# overdrive.net
KiCad netlist of a schematic drawn in Altium Designer
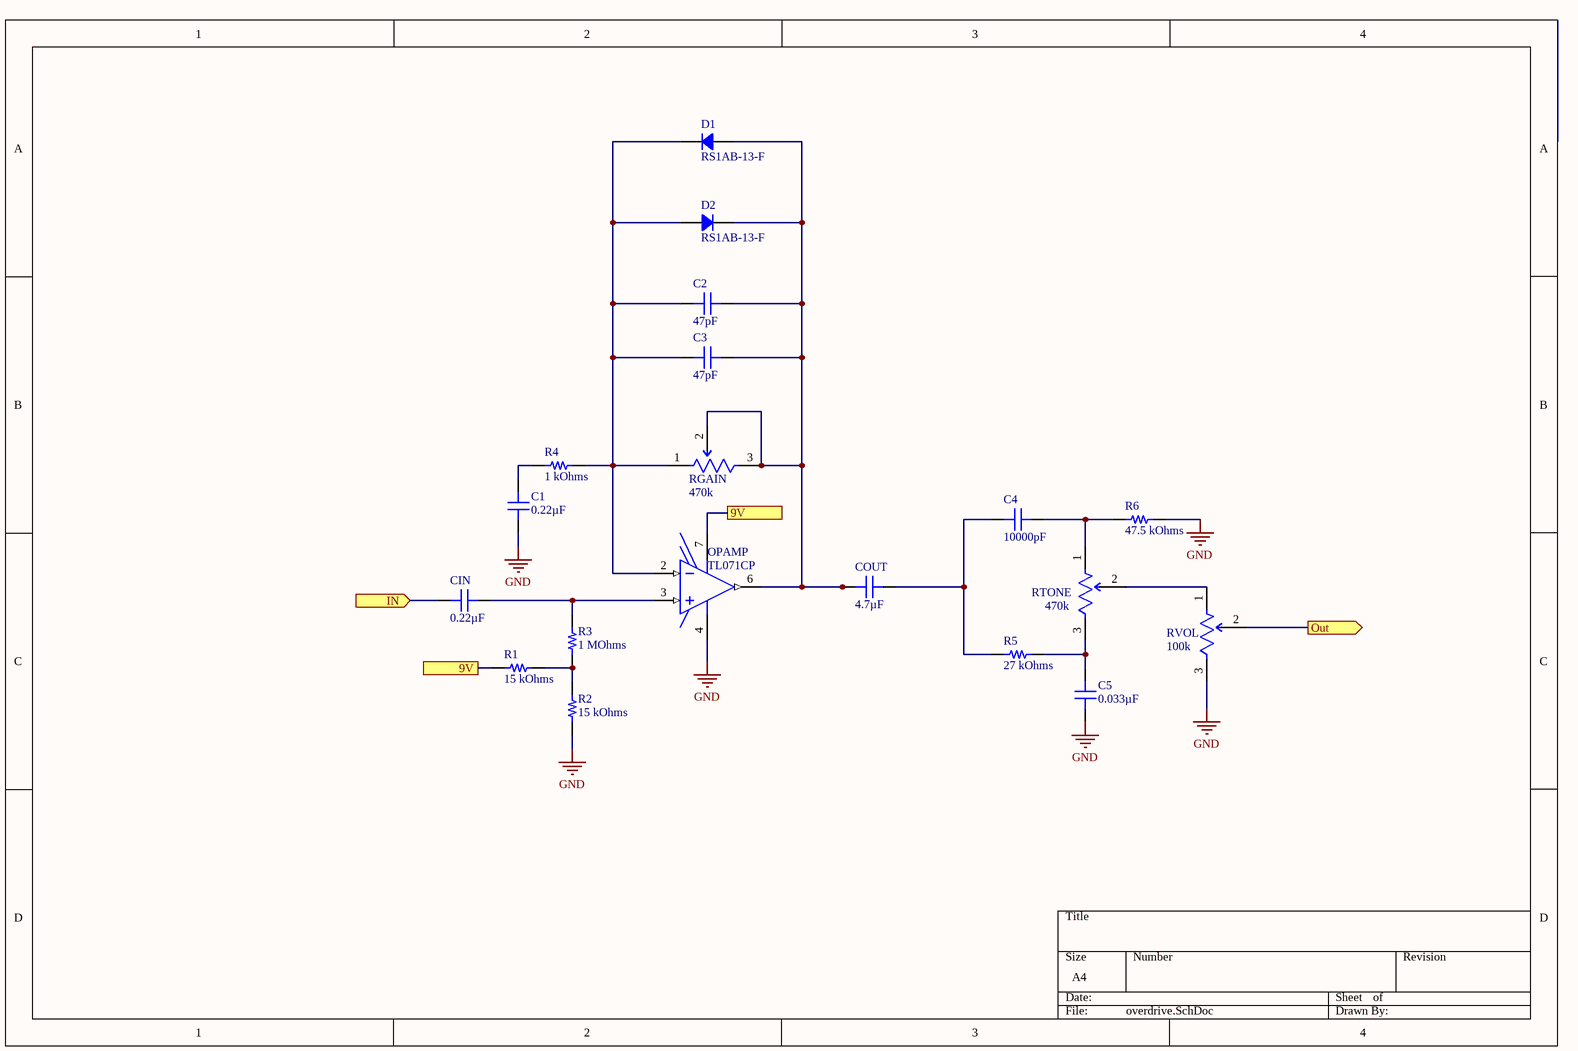
[diagram p0: overdrive.SchDoc]

(export (version "E")
  (design (tool "Eeschema 10.0.6"))
  (components
    (comp (ref "C1")
      (value "0.22µF")
      (footprint "CAP 0402_1005")
      (description "CAP CER 0.22UF 16V X5R 0402")
      (fields (field (name "PART NUMBER") "0402BW224K160YT") (field (name "MANUFACTURER") "Knowles Novacap"))
      (libsource (lib "Celestial Altium Library - altium_library") (part "Capacitor"))
    )
    (comp (ref "C2")
      (value "47pF")
      (footprint "CAP 01005_0402")
      (description "CAP CER 47PF 25V C0G/NP0 01005")
      (fields
        (field (name "PART NUMBER") "GRM0225C1E470GA02L")
        (field (name "MANUFACTURER") "Murata Electronics")
      )
      (libsource (lib "Celestial Altium Library - altium_library") (part "Capacitor"))
    )
    (comp (ref "C3")
      (value "47pF")
      (footprint "CAP 01005_0402")
      (description "CAP CER 47PF 25V C0G/NP0 01005")
      (fields
        (field (name "PART NUMBER") "GRM0225C1E470GA02L")
        (field (name "MANUFACTURER") "Murata Electronics")
      )
      (libsource (lib "Celestial Altium Library - altium_library") (part "Capacitor"))
    )
    (comp (ref "C4")
      (value "10000pF")
      (footprint "CAP 0402_1005")
      (description "CAP CER 0402 10NF 16V X7R 10%")
      (fields (field (name "PART NUMBER") "C0402C103K4RECAUTO") (field (name "MANUFACTURER") "KEMET"))
      (libsource (lib "Celestial Altium Library - altium_library") (part "Capacitor"))
    )
    (comp (ref "C5")
      (value "0.033µF")
      (footprint "CAP 0402_1005")
      (description "CAP CER 0.033UF 25V X7R 0402")
      (fields
        (field (name "PART NUMBER") "0402B333K250CT")
        (field (name "MANUFACTURER") "Walsin Technology Corporation")
      )
      (libsource (lib "Celestial Altium Library - altium_library") (part "Capacitor"))
    )
    (comp (ref "CIN")
      (value "0.22µF")
      (footprint "CAP 0402_1005")
      (description "CAP CER 0.22UF 16V X5R 0402")
      (fields (field (name "PART NUMBER") "0402BW224K160YT") (field (name "MANUFACTURER") "Knowles Novacap"))
      (libsource (lib "Celestial Altium Library - altium_library") (part "Capacitor"))
    )
    (comp (ref "COUT")
      (value "4.7µF")
      (footprint "CAP 0402_1005")
      (description "CAP CER 4.7UF 16V X5R 0402")
      (fields
        (field (name "PART NUMBER") "CL05A475MO5NUNC")
        (field (name "MANUFACTURER") "Samsung Electro-Mechanics")
      )
      (libsource (lib "Celestial Altium Library - altium_library") (part "Capacitor"))
    )
    (comp (ref "D1")
      (value "RS1AB-13-F")
      (footprint "DO214AA SMB")
      (description "DIODE GEN PURP 50V 1A SMB")
      (fields (field (name "MANUFACTURER") "Diodes Incorporated"))
      (libsource (lib "Celestial Altium Library - altium_library") (part "Diode"))
    )
    (comp (ref "D2")
      (value "RS1AB-13-F")
      (footprint "DO214AA SMB")
      (description "DIODE GEN PURP 50V 1A SMB")
      (fields (field (name "MANUFACTURER") "Diodes Incorporated"))
      (libsource (lib "Celestial Altium Library - altium_library") (part "Diode"))
    )
    (comp (ref "OPAMP")
      (value "TL071CP")
      (footprint "P0008A")
      (fields (field (name "MANUFACTURER") "Texas Instruments"))
      (libsource (lib "Components - 10.09.20 - 00.06") (part "CMP-0017-00972-2"))
    )
    (comp (ref "R1")
      (value "15 kOhms")
      (footprint "RES 0201_0603")
      (description "RES 15K OHM 5% 1/20W 0201")
      (fields
        (field (name "PART NUMBER") "RK73B1HTTC153J")
        (field (name "MANUFACTURER") "KOA Speer Electronics, Inc.")
      )
      (libsource (lib "Celestial Altium Library - altium_library") (part "Resistor"))
    )
    (comp (ref "R2")
      (value "15 kOhms")
      (footprint "RES 0201_0603")
      (description "RES 15K OHM 5% 1/20W 0201")
      (fields
        (field (name "PART NUMBER") "RK73B1HTTC153J")
        (field (name "MANUFACTURER") "KOA Speer Electronics, Inc.")
      )
      (libsource (lib "Celestial Altium Library - altium_library") (part "Resistor"))
    )
    (comp (ref "R3")
      (value "1 MOhms")
      (footprint "RES 0201_0603")
      (description "RES 1M OHM 5% 1/20W 0201")
      (fields
        (field (name "PART NUMBER") "RMCF0201JT1M00")
        (field (name "MANUFACTURER") "Stackpole Electronics Inc")
      )
      (libsource (lib "Celestial Altium Library - altium_library") (part "Resistor"))
    )
    (comp (ref "R4")
      (value "1 kOhms")
      (footprint "RES 0201_0603")
      (description "RES 1K OHM 5% 1/20W 0201")
      (fields
        (field (name "PART NUMBER") "RMCF0201JT1K00")
        (field (name "MANUFACTURER") "Stackpole Electronics Inc")
      )
      (libsource (lib "Celestial Altium Library - altium_library") (part "Resistor"))
    )
    (comp (ref "R5")
      (value "27 kOhms")
      (footprint "RES 0201_0603")
      (description "RES 27K OHM 5% 1/20W 0201")
      (fields
        (field (name "PART NUMBER") "RK73B1HTTC273J")
        (field (name "MANUFACTURER") "KOA Speer Electronics, Inc.")
      )
      (libsource (lib "Celestial Altium Library - altium_library") (part "Resistor"))
    )
    (comp (ref "R6")
      (value "47.5 kOhms")
      (footprint "RES 0201_0603")
      (description "RES 47.5K OHM 1% 1/20W 0201")
      (fields
        (field (name "PART NUMBER") "RK73H1HTTC4752F")
        (field (name "MANUFACTURER") "KOA Speer Electronics, Inc.")
      )
      (libsource (lib "Celestial Altium Library - altium_library") (part "Resistor"))
    )
    (comp (ref "RGAIN")
      (value "470k")
      (footprint "FP-3310R-MFG")
      (description "470k -0k")
      (fields (field (name "TOLERANCE") "20%"))
      (libsource (lib "potentiometer") (part "CMP-07234-000023-1"))
    )
    (comp (ref "RTONE")
      (value "470k")
      (footprint "FP-3310R-MFG")
      (description "470k -0k")
      (fields (field (name "TOLERANCE") "20%"))
      (libsource (lib "potentiometer") (part "CMP-07234-000023-1"))
    )
    (comp (ref "RVOL")
      (value "100k")
      (footprint "FP-3310R-MFG")
      (description "100k -0k")
      (fields (field (name "TOLERANCE") "20%"))
      (libsource (lib "potentiometer") (part "CMP-07234-000023-1"))
    )
  )
  (nets
    (net (code "1") (name "/9V") (class "Default")
      (node (ref "OPAMP") (pin "7") (pinfunction "VCC+_7") (pintype "power_in"))
      (node (ref "R1") (pin "1") (pinfunction "1_1") (pintype "passive"))
    )
    (net (code "2") (name "/IN") (class "Default")
      (node (ref "CIN") (pin "1") (pinfunction "1_1") (pintype "passive"))
    )
    (net (code "3") (name "/Out") (class "Default")
      (node (ref "RVOL") (pin "2") (pinfunction "2_2") (pintype "passive"))
    )
    (net (code "4") (name "GND") (class "Default")
      (node (ref "C1") (pin "2") (pinfunction "2_2") (pintype "passive"))
      (node (ref "C5") (pin "1") (pinfunction "1_1") (pintype "passive"))
      (node (ref "OPAMP") (pin "4") (pinfunction "VCC-_4") (pintype "power_in"))
      (node (ref "R2") (pin "1") (pinfunction "1_1") (pintype "passive"))
      (node (ref "R6") (pin "2") (pinfunction "2_2") (pintype "passive"))
      (node (ref "RVOL") (pin "3") (pinfunction "CW_3") (pintype "passive"))
    )
    (net (code "5") (name "Net-(C1-Pad1)") (class "Default")
      (node (ref "C1") (pin "1") (pinfunction "1_1") (pintype "passive"))
      (node (ref "R4") (pin "1") (pinfunction "1_1") (pintype "passive"))
    )
    (net (code "6") (name "Net-(C4-Pad2)") (class "Default")
      (node (ref "C4") (pin "2") (pinfunction "2_2") (pintype "passive"))
      (node (ref "COUT") (pin "2") (pinfunction "2_2") (pintype "passive"))
      (node (ref "R5") (pin "1") (pinfunction "1_1") (pintype "passive"))
    )
    (net (code "7") (name "Net-(OPAMP-IN+)") (class "Default")
      (node (ref "CIN") (pin "2") (pinfunction "2_2") (pintype "passive"))
      (node (ref "OPAMP") (pin "3") (pinfunction "IN+_3") (pintype "input"))
      (node (ref "R3") (pin "1") (pinfunction "1_1") (pintype "passive"))
    )
    (net (code "8") (name "Net-(OPAMP-IN-)") (class "Default")
      (node (ref "C2") (pin "1") (pinfunction "1_1") (pintype "passive"))
      (node (ref "C3") (pin "1") (pinfunction "1_1") (pintype "passive"))
      (node (ref "D1") (pin "2") (pinfunction "2_2") (pintype "passive"))
      (node (ref "D2") (pin "1") (pinfunction "1_1") (pintype "passive"))
      (node (ref "OPAMP") (pin "2") (pinfunction "IN-_2") (pintype "input"))
      (node (ref "R4") (pin "2") (pinfunction "2_2") (pintype "passive"))
      (node (ref "RGAIN") (pin "1") (pinfunction "CCW_1") (pintype "passive"))
    )
    (net (code "9") (name "Net-(OPAMP-OUT)") (class "Default")
      (node (ref "C2") (pin "2") (pinfunction "2_2") (pintype "passive"))
      (node (ref "C3") (pin "2") (pinfunction "2_2") (pintype "passive"))
      (node (ref "COUT") (pin "1") (pinfunction "1_1") (pintype "passive"))
      (node (ref "D1") (pin "1") (pinfunction "1_1") (pintype "passive"))
      (node (ref "D2") (pin "2") (pinfunction "2_2") (pintype "passive"))
      (node (ref "OPAMP") (pin "6") (pinfunction "OUT_6") (pintype "output"))
      (node (ref "RGAIN") (pin "2") (pinfunction "2_2") (pintype "passive"))
      (node (ref "RGAIN") (pin "3") (pinfunction "CW_3") (pintype "passive"))
    )
    (net (code "10") (name "Net-(R1-Pad2)") (class "Default")
      (node (ref "R1") (pin "2") (pinfunction "2_2") (pintype "passive"))
      (node (ref "R2") (pin "2") (pinfunction "2_2") (pintype "passive"))
      (node (ref "R3") (pin "2") (pinfunction "2_2") (pintype "passive"))
    )
    (net (code "11") (name "Net-(RTONE-CCW)") (class "Default")
      (node (ref "C4") (pin "1") (pinfunction "1_1") (pintype "passive"))
      (node (ref "R6") (pin "1") (pinfunction "1_1") (pintype "passive"))
      (node (ref "RTONE") (pin "1") (pinfunction "CCW_1") (pintype "passive"))
    )
    (net (code "12") (name "Net-(RTONE-CW)") (class "Default")
      (node (ref "C5") (pin "2") (pinfunction "2_2") (pintype "passive"))
      (node (ref "R5") (pin "2") (pinfunction "2_2") (pintype "passive"))
      (node (ref "RTONE") (pin "3") (pinfunction "CW_3") (pintype "passive"))
    )
    (net (code "13") (name "Net-(RVOL-CCW)") (class "Default")
      (node (ref "RTONE") (pin "2") (pinfunction "2_2") (pintype "passive"))
      (node (ref "RVOL") (pin "1") (pinfunction "CCW_1") (pintype "passive"))
    )
    (net (code "14") (name "unconnected-(OPAMP-NC-Pad8)") (class "Default")
      (node (ref "OPAMP") (pin "8") (pinfunction "NC_8") (pintype "passive"))
    )
    (net (code "15") (name "unconnected-(OPAMP-OFFSET_N1-Pad1)") (class "Default")
      (node (ref "OPAMP") (pin "1") (pinfunction "OFFSET_N1_1") (pintype "input"))
    )
    (net (code "16") (name "unconnected-(OPAMP-OFFSET_N2-Pad5)") (class "Default")
      (node (ref "OPAMP") (pin "5") (pinfunction "OFFSET_N2_5") (pintype "input"))
    )
  )
)
